# Encoder1.net
KiCad netlist of a schematic drawn in Altium Designer
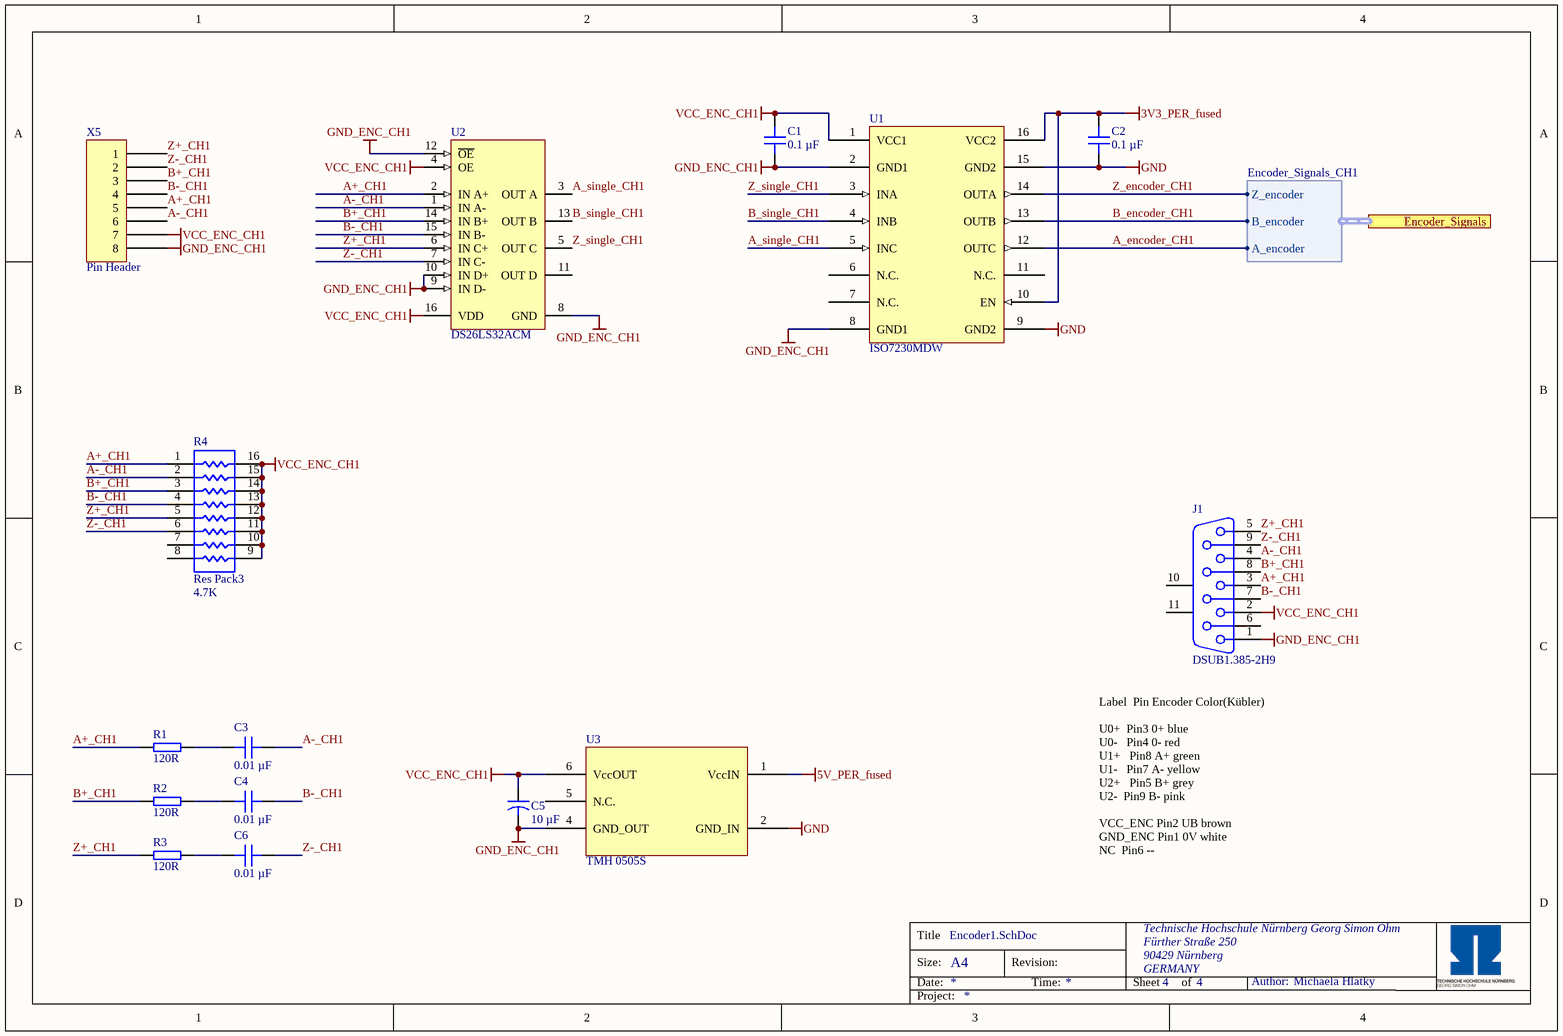
[diagram p0: Encoder1.SchDoc]

(export (version "E")
  (design (tool "Eeschema 10.0.6"))
  (components
    (comp (ref "C1")
      (value "0.1 µF")
      (footprint "C_0805")
      (description "Capacitor 0805, 50 VDC, 0.1 µF, X7R")
      (fields
        (field (name "MANUFACTURER PART NUMBER") "C0805C104J5RECTU")
        (field (name "MANUFACTURER") "KEMET")
        (field (name "CREATED FROM") "MGremer")
      )
      (libsource (lib "user") (part "Capacitor"))
    )
    (comp (ref "C2")
      (value "0.1 µF")
      (footprint "C_0805")
      (description "Capacitor 0805, 50 VDC, 0.1 µF, X7R")
      (fields
        (field (name "MANUFACTURER PART NUMBER") "C0805C104J5RECTU")
        (field (name "MANUFACTURER") "KEMET")
        (field (name "CREATED FROM") "MGremer")
      )
      (libsource (lib "user") (part "Capacitor"))
    )
    (comp (ref "C3")
      (value "0.01 µF")
      (footprint "C_0805")
      (description "Capacitor 0805, 100 VDC, 0.01 µF, X7R")
      (fields
        (field (name "MANUFACTURER PART NUMBER") "GRM21BR72A103KA01L")
        (field (name "MANUFACTURER") "Murata Electronics")
        (field (name "CREATED FROM") "MGremer")
      )
      (libsource (lib "user") (part "Capacitor"))
    )
    (comp (ref "C4")
      (value "0.01 µF")
      (footprint "C_0805")
      (description "Capacitor 0805, 100 VDC, 0.01 µF, X7R")
      (fields
        (field (name "MANUFACTURER PART NUMBER") "GRM21BR72A103KA01L")
        (field (name "MANUFACTURER") "Murata Electronics")
        (field (name "CREATED FROM") "MGremer")
      )
      (libsource (lib "user") (part "Capacitor"))
    )
    (comp (ref "C5")
      (value "10 µF")
      (footprint "CAPR5-4X5")
      (description "Capacitor; 2 Leads")
      (fields
        (field (name "MANUFACTURER PART NUMBER") "CAPR5-4X5")
        (field (name "PUBLISHER") "Altium Limited")
        (field (name "CREATED FROM") "MHlatky")
      )
      (libsource (lib "user") (part "Cap2"))
    )
    (comp (ref "C6")
      (value "0.01 µF")
      (footprint "C_0805")
      (description "Capacitor 0805, 100 VDC, 0.01 µF, X7R")
      (fields
        (field (name "MANUFACTURER PART NUMBER") "GRM21BR72A103KA01L")
        (field (name "MANUFACTURER") "Murata Electronics")
        (field (name "CREATED FROM") "MGremer")
      )
      (libsource (lib "user") (part "Capacitor"))
    )
    (comp (ref "J1")
      (value "DSUB1.385-2H9")
      (footprint "DSUB1.385-2H9")
      (description "Connector; D Subminiature; 9 Position; Right Angle; Pitch 1.385 mm")
      (fields
        (field (name "MANUFACTURER") "Altium")
        (field (name "PUBLISHER") "Altium Limited")
        (field (name "CREATED FROM") "MHlatky")
      )
      (libsource (lib "user") (part "D Connector 9"))
    )
    (comp (ref "R1")
      (value "120R")
      (footprint "RES 0603_1608")
      (description "SMD resistor E24 series")
      (fields
        (field (name "MANUFACTURER PART NUMBER") "RK73B1JTTD121J")
        (field (name "MANUFACTURER") "KOA Speer")
        (field (name "CREATED FROM") "MGremer")
      )
      (libsource (lib "user") (part "Resistor"))
    )
    (comp (ref "R2")
      (value "120R")
      (footprint "RES 0603_1608")
      (description "SMD resistor E24 series")
      (fields
        (field (name "MANUFACTURER PART NUMBER") "RK73B1JTTD121J")
        (field (name "MANUFACTURER") "KOA Speer")
        (field (name "CREATED FROM") "MGremer")
      )
      (libsource (lib "user") (part "Resistor"))
    )
    (comp (ref "R3")
      (value "120R")
      (footprint "RES 0603_1608")
      (description "SMD resistor E24 series")
      (fields
        (field (name "MANUFACTURER PART NUMBER") "RK73B1JTTD121J")
        (field (name "MANUFACTURER") "KOA Speer")
        (field (name "CREATED FROM") "MGremer")
      )
      (libsource (lib "user") (part "Resistor"))
    )
    (comp (ref "R4")
      (value "Res Pack3")
      (footprint "SO-16_N")
      (description "SOIC, 16-Leads, Body 9.9x3.9mm, Pitch 1.27mm, IPC Medium Density")
      (fields
        (field (name "ALTIUM_VALUE") "4.7K")
        (field (name "PUBLISHER") "Altium Limited")
        (field (name "CREATED FROM") "MHlatky")
      )
      (libsource (lib "user") (part "Res Pack3"))
    )
    (comp (ref "U1")
      (value "ISO7230MDW")
      (footprint "TI ISO7230 SOIC")
      (description "ISO723xx High-Speed, Triple-Channel Digital Isolators")
      (fields (field (name "MANUFACTURER") "Analog Devices") (field (name "CREATED FROM") "MHlatky"))
      (libsource (lib "user") (part "TI ISO7230"))
    )
    (comp (ref "U2")
      (value "DS26LS32ACM")
      (footprint "M16A_M")
      (description "DS26LS32AC/DS26LS32C/DS26LS32M/DS26LS33M Quad Differential Line Receivers")
      (fields
        (field (name "MANUFACTURER") "Texas Instruments")
        (field (name "PUBLISHER") "Altium Limited")
        (field (name "CREATED FROM") "MHlatky")
      )
      (libsource (lib "user") (part "DS26LS32ACM"))
    )
    (comp (ref "U3")
      (value "TMH 0505S")
      (footprint "SIL-6(7)")
      (fields (field (name "MANUFACTURER") "Traco") (field (name "CREATED FROM") "MHlatky"))
      (libsource (lib "user") (part "TRACO TMH 0505S"))
    )
    (comp (ref "X5")
      (value "Pin Header")
      (footprint "HDR1X8")
      (description "8 Pin")
      (fields (field (name "MANUFACTURER PART NUMBER") "HDR1X8") (field (name "CREATED FROM") "MHlatky"))
      (libsource (lib "user") (part "8 Pin"))
    )
  )
  (nets
    (net (code "2") (name "/A+_CH1") (class "Default")
      (node (ref "J1") (pin "3") (pinfunction "3_3") (pintype "passive"))
      (node (ref "R1") (pin "1") (pinfunction "1_1") (pintype "passive"))
      (node (ref "R4") (pin "1") (pinfunction "1_1") (pintype "passive"))
      (node (ref "U2") (pin "2") (pinfunction "IN_A+_2") (pintype "input"))
      (node (ref "X5") (pin "5") (pinfunction "5_5") (pintype "passive"))
    )
    (net (code "3") (name "/A-_CH1") (class "Default")
      (node (ref "C3") (pin "2") (pinfunction "2_2") (pintype "passive"))
      (node (ref "J1") (pin "4") (pinfunction "4_4") (pintype "passive"))
      (node (ref "R4") (pin "2") (pinfunction "2_2") (pintype "passive"))
      (node (ref "U2") (pin "1") (pinfunction "IN_A-_1") (pintype "input"))
      (node (ref "X5") (pin "6") (pinfunction "6_6") (pintype "passive"))
    )
    (net (code "4") (name "/A_encoder_CH1") (class "Default")
      (node (ref "U1") (pin "12") (pinfunction "OUTC_12") (pintype "output"))
    )
    (net (code "5") (name "/A_single_CH1") (class "Default")
      (node (ref "U1") (pin "5") (pinfunction "INC_5") (pintype "input"))
      (node (ref "U2") (pin "3") (pinfunction "OUT_A_3") (pintype "tri_state"))
    )
    (net (code "6") (name "/B+_CH1") (class "Default")
      (node (ref "J1") (pin "8") (pinfunction "8_8") (pintype "passive"))
      (node (ref "R2") (pin "1") (pinfunction "1_1") (pintype "passive"))
      (node (ref "R4") (pin "3") (pinfunction "3_3") (pintype "passive"))
      (node (ref "U2") (pin "14") (pinfunction "IN_B+_14") (pintype "input"))
      (node (ref "X5") (pin "3") (pinfunction "3_3") (pintype "passive"))
    )
    (net (code "7") (name "/B-_CH1") (class "Default")
      (node (ref "C4") (pin "2") (pinfunction "2_2") (pintype "passive"))
      (node (ref "J1") (pin "7") (pinfunction "7_7") (pintype "passive"))
      (node (ref "R4") (pin "4") (pinfunction "4_4") (pintype "passive"))
      (node (ref "U2") (pin "15") (pinfunction "IN_B-_15") (pintype "input"))
      (node (ref "X5") (pin "4") (pinfunction "4_4") (pintype "passive"))
    )
    (net (code "8") (name "/B_encoder_CH1") (class "Default")
      (node (ref "U1") (pin "13") (pinfunction "OUTB_13") (pintype "output"))
    )
    (net (code "9") (name "/B_single_CH1") (class "Default")
      (node (ref "U1") (pin "4") (pinfunction "INB_4") (pintype "input"))
      (node (ref "U2") (pin "13") (pinfunction "OUT_B_13") (pintype "tri_state"))
    )
    (net (code "10") (name "/Z+_CH1") (class "Default")
      (node (ref "J1") (pin "5") (pinfunction "5_5") (pintype "passive"))
      (node (ref "R3") (pin "1") (pinfunction "1_1") (pintype "passive"))
      (node (ref "R4") (pin "5") (pinfunction "5_5") (pintype "passive"))
      (node (ref "U2") (pin "6") (pinfunction "IN_C+_6") (pintype "input"))
      (node (ref "X5") (pin "1") (pinfunction "1_1") (pintype "passive"))
    )
    (net (code "11") (name "/Z-_CH1") (class "Default")
      (node (ref "C6") (pin "2") (pinfunction "2_2") (pintype "passive"))
      (node (ref "J1") (pin "9") (pinfunction "9_9") (pintype "passive"))
      (node (ref "R4") (pin "6") (pinfunction "6_6") (pintype "passive"))
      (node (ref "U2") (pin "7") (pinfunction "IN_C-_7") (pintype "input"))
      (node (ref "X5") (pin "2") (pinfunction "2_2") (pintype "passive"))
    )
    (net (code "12") (name "/Z_encoder_CH1") (class "Default")
      (node (ref "U1") (pin "14") (pinfunction "OUTA_14") (pintype "output"))
    )
    (net (code "13") (name "/Z_single_CH1") (class "Default")
      (node (ref "U1") (pin "3") (pinfunction "INA_3") (pintype "input"))
      (node (ref "U2") (pin "5") (pinfunction "OUT_C_5") (pintype "tri_state"))
    )
    (net (code "15") (name "3V3_PER_fused") (class "Default")
      (node (ref "C2") (pin "2") (pinfunction "2_2") (pintype "passive"))
      (node (ref "U1") (pin "10") (pinfunction "EN_10") (pintype "input"))
      (node (ref "U1") (pin "16") (pinfunction "VCC2_16") (pintype "passive"))
    )
    (net (code "16") (name "5V_PER_fused") (class "Default")
      (node (ref "U3") (pin "1") (pinfunction "VccIN_1") (pintype "passive"))
    )
    (net (code "17") (name "GND") (class "Default")
      (node (ref "C2") (pin "1") (pinfunction "1_1") (pintype "passive"))
      (node (ref "U1") (pin "15") (pinfunction "GND2_15") (pintype "passive"))
      (node (ref "U1") (pin "9") (pinfunction "GND2_9") (pintype "passive"))
      (node (ref "U3") (pin "2") (pinfunction "GND_IN_2") (pintype "passive"))
    )
    (net (code "18") (name "GND_ENC_CH1") (class "Default")
      (node (ref "C1") (pin "1") (pinfunction "1_1") (pintype "passive"))
      (node (ref "C5") (pin "2") (pinfunction "2_2") (pintype "passive"))
      (node (ref "J1") (pin "1") (pinfunction "1_1") (pintype "passive"))
      (node (ref "U1") (pin "2") (pinfunction "GND1_2") (pintype "passive"))
      (node (ref "U1") (pin "8") (pinfunction "GND1_8") (pintype "passive"))
      (node (ref "U2") (pin "10") (pinfunction "IN_D+_10") (pintype "input"))
      (node (ref "U2") (pin "12") (pinfunction "~{OE}_12") (pintype "input"))
      (node (ref "U2") (pin "8") (pinfunction "GND_8") (pintype "power_in"))
      (node (ref "U2") (pin "9") (pinfunction "IN_D-_9") (pintype "input"))
      (node (ref "U3") (pin "4") (pinfunction "GND_OUT_4") (pintype "passive"))
      (node (ref "X5") (pin "8") (pinfunction "8_8") (pintype "passive"))
    )
    (net (code "19") (name "Net-(C3-Pad1)") (class "Default")
      (node (ref "C3") (pin "1") (pinfunction "1_1") (pintype "passive"))
      (node (ref "R1") (pin "2") (pinfunction "2_2") (pintype "passive"))
    )
    (net (code "20") (name "Net-(C4-Pad1)") (class "Default")
      (node (ref "C4") (pin "1") (pinfunction "1_1") (pintype "passive"))
      (node (ref "R2") (pin "2") (pinfunction "2_2") (pintype "passive"))
    )
    (net (code "21") (name "Net-(C6-Pad1)") (class "Default")
      (node (ref "C6") (pin "1") (pinfunction "1_1") (pintype "passive"))
      (node (ref "R3") (pin "2") (pinfunction "2_2") (pintype "passive"))
    )
    (net (code "22") (name "VCC_ENC_CH1") (class "Default")
      (node (ref "C1") (pin "2") (pinfunction "2_2") (pintype "passive"))
      (node (ref "C5") (pin "1") (pinfunction "1_1") (pintype "passive"))
      (node (ref "J1") (pin "2") (pinfunction "2_2") (pintype "passive"))
      (node (ref "R4") (pin "10") (pinfunction "10_10") (pintype "passive"))
      (node (ref "R4") (pin "11") (pinfunction "11_11") (pintype "passive"))
      (node (ref "R4") (pin "12") (pinfunction "12_12") (pintype "passive"))
      (node (ref "R4") (pin "13") (pinfunction "13_13") (pintype "passive"))
      (node (ref "R4") (pin "14") (pinfunction "14_14") (pintype "passive"))
      (node (ref "R4") (pin "15") (pinfunction "15_15") (pintype "passive"))
      (node (ref "R4") (pin "16") (pinfunction "16_16") (pintype "passive"))
      (node (ref "R4") (pin "9") (pinfunction "9_9") (pintype "passive"))
      (node (ref "U1") (pin "1") (pinfunction "VCC1_1") (pintype "passive"))
      (node (ref "U2") (pin "16") (pinfunction "VDD_16") (pintype "power_in"))
      (node (ref "U2") (pin "4") (pinfunction "OE_4") (pintype "input"))
      (node (ref "U3") (pin "6") (pinfunction "VccOUT_6") (pintype "passive"))
      (node (ref "X5") (pin "7") (pinfunction "7_7") (pintype "passive"))
    )
    (net (code "23") (name "unconnected-(J1-MH1-Pad10)") (class "Default")
      (node (ref "J1") (pin "10") (pinfunction "MH1_10") (pintype "passive"))
    )
    (net (code "24") (name "unconnected-(J1-MH2-Pad11)") (class "Default")
      (node (ref "J1") (pin "11") (pinfunction "MH2_11") (pintype "passive"))
    )
    (net (code "25") (name "unconnected-(J1-Pad6)") (class "Default")
      (node (ref "J1") (pin "6") (pinfunction "6_6") (pintype "passive"))
    )
    (net (code "26") (name "unconnected-(R4-Pad7)") (class "Default")
      (node (ref "R4") (pin "7") (pinfunction "7_7") (pintype "passive"))
    )
    (net (code "27") (name "unconnected-(R4-Pad8)") (class "Default")
      (node (ref "R4") (pin "8") (pinfunction "8_8") (pintype "passive"))
    )
    (net (code "28") (name "unconnected-(U1-N.C.-Pad6)") (class "Default")
      (node (ref "U1") (pin "6") (pinfunction "N.C._6") (pintype "passive"))
    )
    (net (code "29") (name "unconnected-(U1-N.C.-Pad7)") (class "Default")
      (node (ref "U1") (pin "7") (pinfunction "N.C._7") (pintype "passive"))
    )
    (net (code "30") (name "unconnected-(U1-N.C.-Pad11)") (class "Default")
      (node (ref "U1") (pin "11") (pinfunction "N.C._11") (pintype "passive"))
    )
    (net (code "31") (name "unconnected-(U2-OUT_D-Pad11)") (class "Default")
      (node (ref "U2") (pin "11") (pinfunction "OUT_D_11") (pintype "tri_state"))
    )
    (net (code "32") (name "unconnected-(U3-N.C.-Pad5)") (class "Default")
      (node (ref "U3") (pin "5") (pinfunction "N.C._5") (pintype "passive"))
    )
  )
)
